# ScopeX.net
KiCad netlist of a schematic drawn in EAGLE
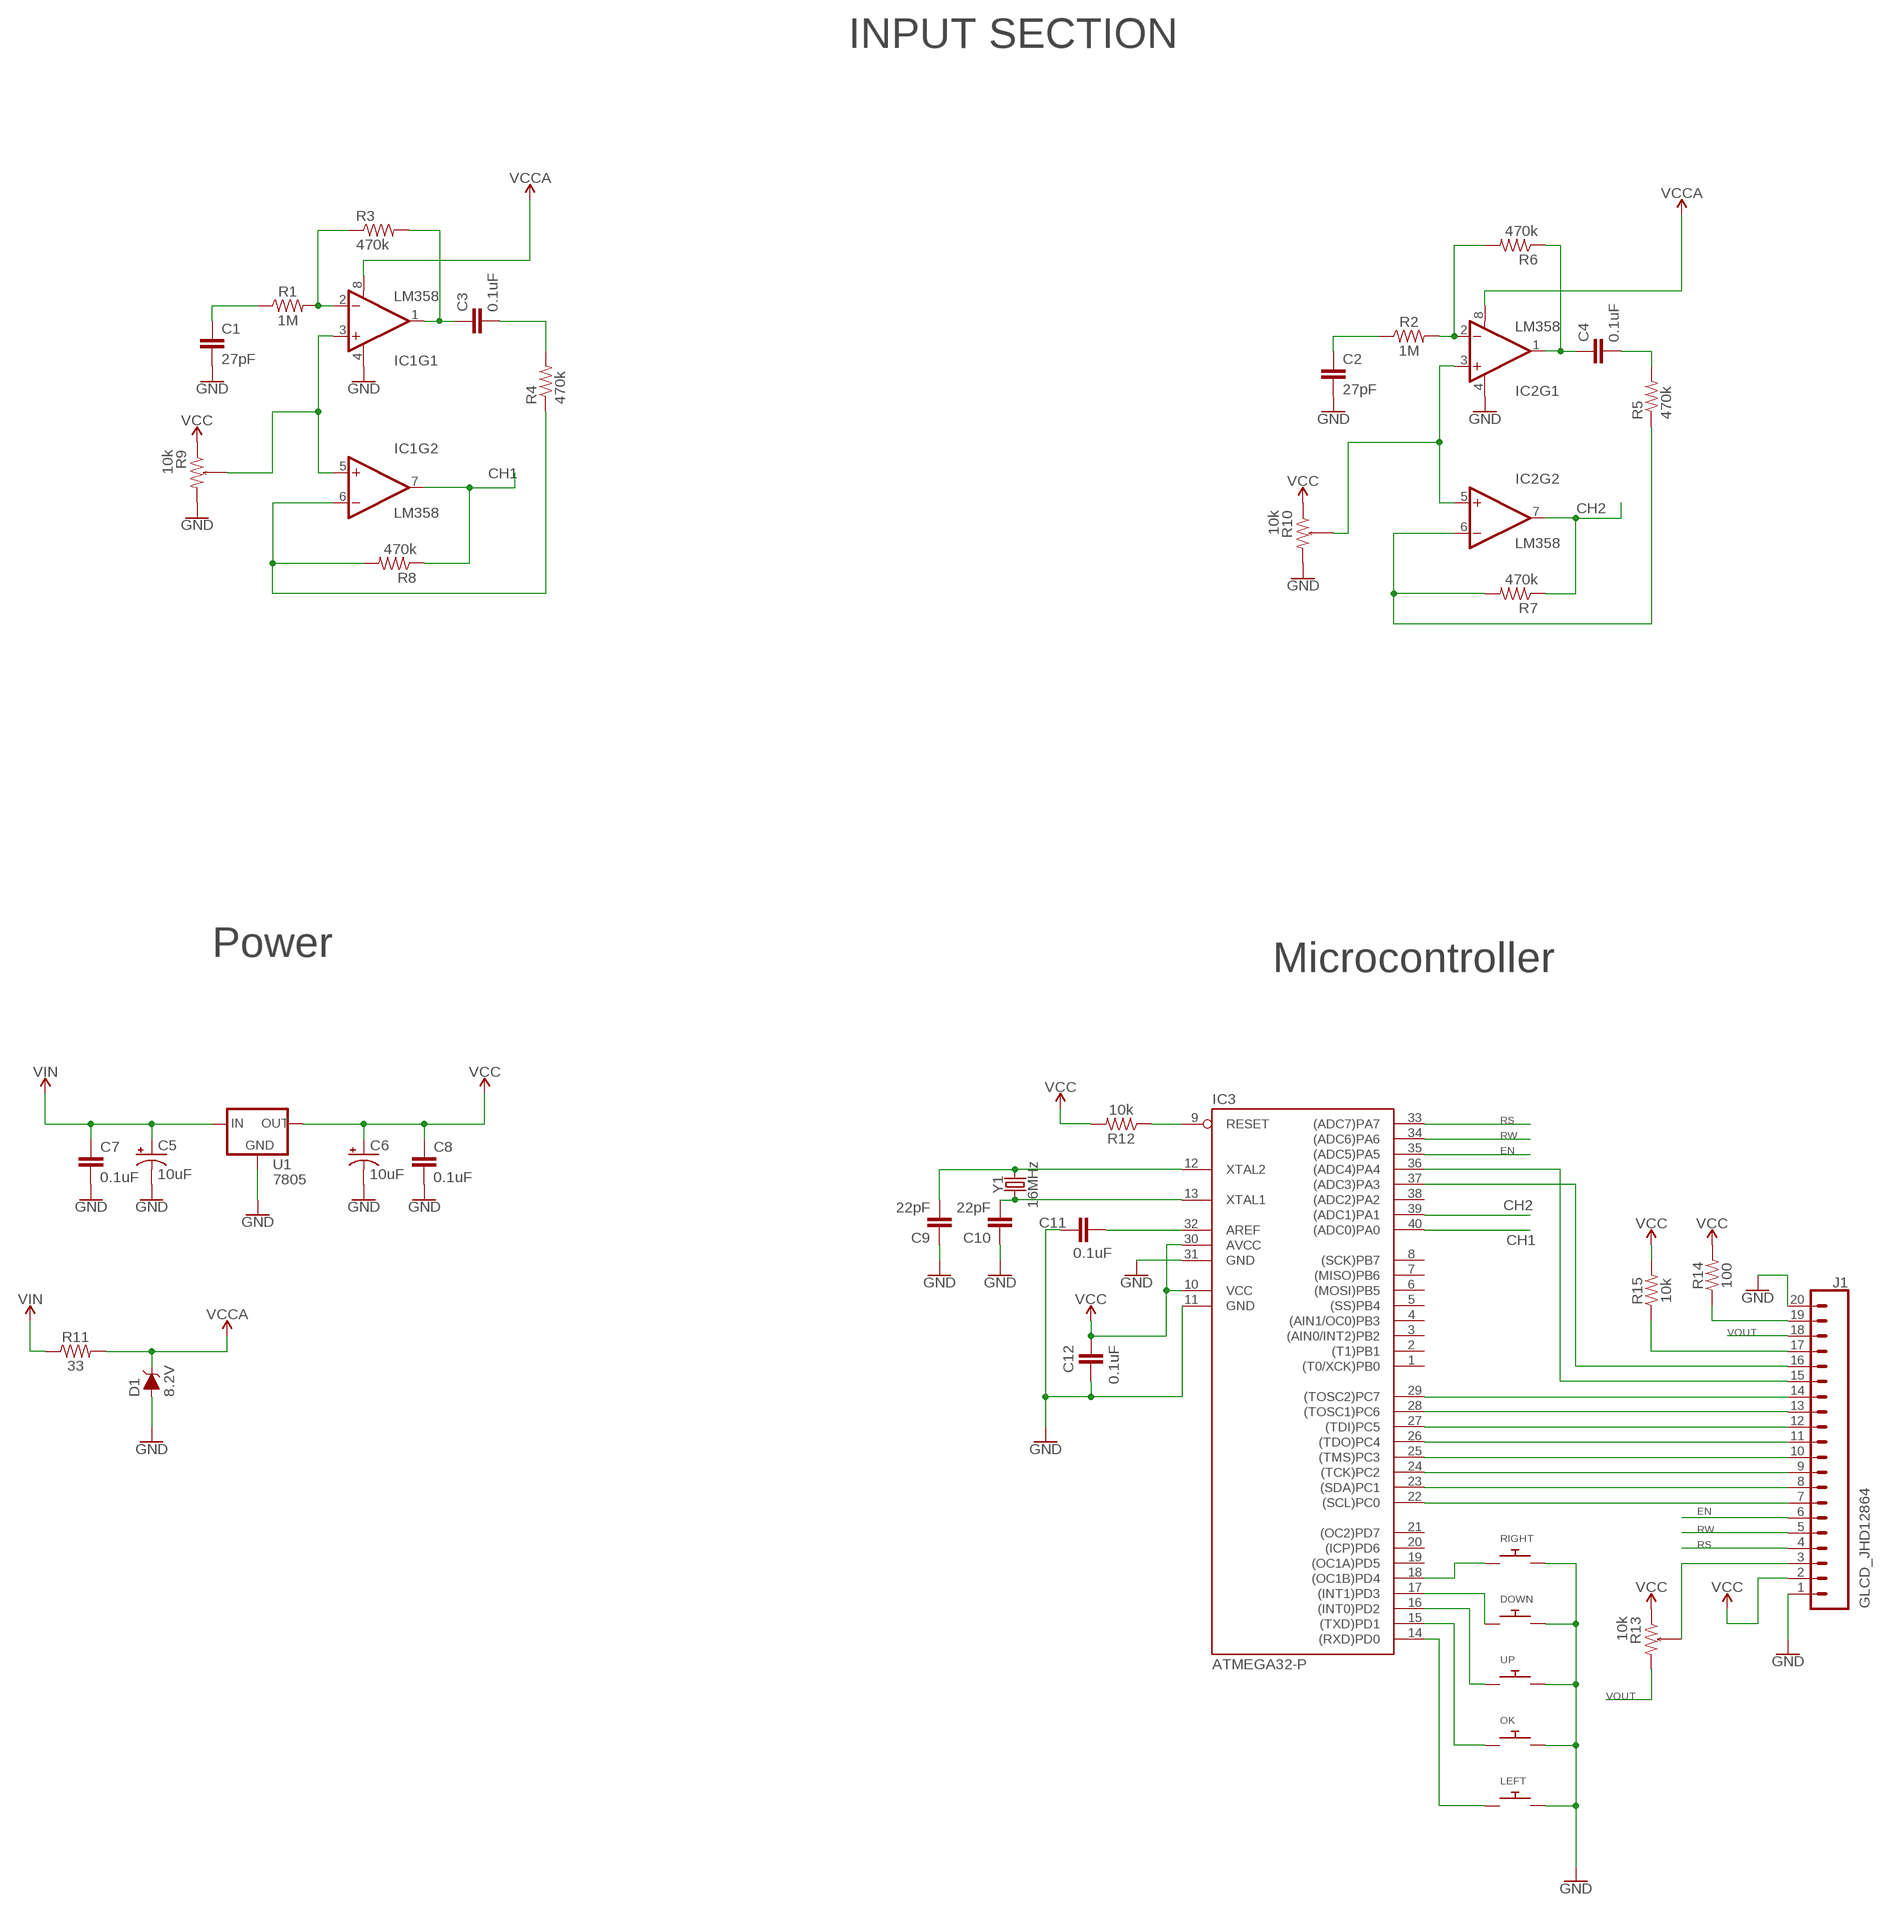
[diagram p0: schematic, sheet 1]

(export (version "E")
  (design (tool "Eeschema 10.0.6"))
  (components
    (comp (ref "C1")
      (value "27pF")
      (footprint "eagle-import:0603")
      (libsource (lib "eagle-import") (part "27PF-0603-50V-5%"))
    )
    (comp (ref "C2")
      (value "27pF")
      (footprint "eagle-import:0603")
      (libsource (lib "eagle-import") (part "27PF-0603-50V-5%"))
    )
    (comp (ref "C3")
      (value "0.1uF")
      (footprint "eagle-import:0603")
      (libsource (lib "eagle-import") (part "0.1UF-0603-25V-(+80/-20%)"))
    )
    (comp (ref "C4")
      (value "0.1uF")
      (footprint "eagle-import:0603")
      (libsource (lib "eagle-import") (part "0.1UF-0603-25V-(+80/-20%)"))
    )
    (comp (ref "C5")
      (value "10uF")
      (footprint "eagle-import:CPOL-RADIAL-10UF-25V")
      (libsource (lib "eagle-import") (part "CAP_POLPTH2"))
    )
    (comp (ref "C6")
      (value "10uF")
      (footprint "eagle-import:CPOL-RADIAL-10UF-25V")
      (libsource (lib "eagle-import") (part "CAP_POLPTH2"))
    )
    (comp (ref "C7")
      (value "0.1uF")
      (footprint "eagle-import:1206")
      (libsource (lib "eagle-import") (part "CAP1206"))
    )
    (comp (ref "C8")
      (value "0.1uF")
      (footprint "eagle-import:1206")
      (libsource (lib "eagle-import") (part "CAP1206"))
    )
    (comp (ref "C9")
      (value "22pF")
      (footprint "eagle-import:0603")
      (libsource (lib "eagle-import") (part "22PF-0603-50V-5%"))
    )
    (comp (ref "C10")
      (value "22pF")
      (footprint "eagle-import:0603")
      (libsource (lib "eagle-import") (part "22PF-0603-50V-5%"))
    )
    (comp (ref "C11")
      (value "0.1uF")
      (footprint "eagle-import:0603")
      (libsource (lib "eagle-import") (part "0.1UF-0603-25V-(+80/-20%)"))
    )
    (comp (ref "C12")
      (value "0.1uF")
      (footprint "eagle-import:0603")
      (libsource (lib "eagle-import") (part "0.1UF-0603-25V-(+80/-20%)"))
    )
    (comp (ref "D1")
      (value "8.2V")
      (footprint "eagle-import:SOD-323")
      (libsource (lib "eagle-import") (part "DIODE-ZENER-MMSZ5232BS"))
    )
    (comp (ref "DOWN")
      (value "SWITCH_PUSHBUTTONSOFTTOUCHSMD_SJ")
      (footprint "eagle-import:PUSHBUTTON_SMD_SJ")
      (libsource (lib "eagle-import") (part "SWITCH_PUSHBUTTONSOFTTOUCHSMD_SJ"))
    )
    (comp (ref "IC1")
      (value "LM358")
      (footprint "eagle-import:DIP08")
      (libsource (lib "eagle-import") (part "LM358"))
    )
    (comp (ref "IC2")
      (value "LM358")
      (footprint "eagle-import:DIP08")
      (libsource (lib "eagle-import") (part "LM358"))
    )
    (comp (ref "IC3")
      (value "ATMEGA32-P")
      (footprint "eagle-import:DIL40")
      (fields (field (name "MPN") "ATMEGA32-16PU"))
      (libsource (lib "eagle-import") (part "MEGA32-P"))
    )
    (comp (ref "J1")
      (value "GLCD_JHD12864")
      (footprint "eagle-import:1X20")
      (libsource (lib "eagle-import") (part "CONN_20"))
    )
    (comp (ref "LEFT")
      (value "SWITCH_PUSHBUTTONSOFTTOUCHSMD_SJ")
      (footprint "eagle-import:PUSHBUTTON_SMD_SJ")
      (libsource (lib "eagle-import") (part "SWITCH_PUSHBUTTONSOFTTOUCHSMD_SJ"))
    )
    (comp (ref "OK")
      (value "SWITCH_PUSHBUTTONSOFTTOUCHSMD_SJ")
      (footprint "eagle-import:PUSHBUTTON_SMD_SJ")
      (libsource (lib "eagle-import") (part "SWITCH_PUSHBUTTONSOFTTOUCHSMD_SJ"))
    )
    (comp (ref "R1")
      (value "1M")
      (footprint "eagle-import:0603")
      (libsource (lib "eagle-import") (part "1MOHM-0603-1/4W-5%"))
    )
    (comp (ref "R2")
      (value "1M")
      (footprint "eagle-import:0603")
      (libsource (lib "eagle-import") (part "1MOHM-0603-1/4W-5%"))
    )
    (comp (ref "R3")
      (value "470k")
      (footprint "eagle-import:0603-RES")
      (libsource (lib "eagle-import") (part "RESISTOR0603-RES"))
    )
    (comp (ref "R4")
      (value "470k")
      (footprint "eagle-import:0603-RES")
      (libsource (lib "eagle-import") (part "RESISTOR0603-RES"))
    )
    (comp (ref "R5")
      (value "470k")
      (footprint "eagle-import:0603-RES")
      (libsource (lib "eagle-import") (part "RESISTOR0603-RES"))
    )
    (comp (ref "R6")
      (value "470k")
      (footprint "eagle-import:0603-RES")
      (libsource (lib "eagle-import") (part "RESISTOR0603-RES"))
    )
    (comp (ref "R7")
      (value "470k")
      (footprint "eagle-import:0603-RES")
      (libsource (lib "eagle-import") (part "RESISTOR0603-RES"))
    )
    (comp (ref "R8")
      (value "470k")
      (footprint "eagle-import:0603-RES")
      (libsource (lib "eagle-import") (part "RESISTOR0603-RES"))
    )
    (comp (ref "R9")
      (value "10k")
      (footprint "eagle-import:0603-ARV")
      (libsource (lib "eagle-import") (part "POTENTIOMETER"))
    )
    (comp (ref "R10")
      (value "10k")
      (footprint "eagle-import:0603-ARV")
      (libsource (lib "eagle-import") (part "POTENTIOMETER"))
    )
    (comp (ref "R11")
      (value "33")
      (footprint "eagle-import:0603")
      (libsource (lib "eagle-import") (part "33OHM-0603-1/10W-1%"))
    )
    (comp (ref "R12")
      (value "10k")
      (footprint "eagle-import:0603")
      (libsource (lib "eagle-import") (part "10KOHM-0603-1/10W-1%"))
    )
    (comp (ref "R13")
      (value "10k")
      (footprint "eagle-import:0603-ARV")
      (libsource (lib "eagle-import") (part "POTENTIOMETER"))
    )
    (comp (ref "R14")
      (value "100")
      (footprint "eagle-import:0603")
      (libsource (lib "eagle-import") (part "100OHM-0603-1/4W-5%"))
    )
    (comp (ref "R15")
      (value "10k")
      (footprint "eagle-import:0603")
      (libsource (lib "eagle-import") (part "10KOHM-0603-1/10W-1%"))
    )
    (comp (ref "RIGHT")
      (value "SWITCH_PUSHBUTTONSOFTTOUCHSMD_SJ")
      (footprint "eagle-import:PUSHBUTTON_SMD_SJ")
      (libsource (lib "eagle-import") (part "SWITCH_PUSHBUTTONSOFTTOUCHSMD_SJ"))
    )
    (comp (ref "U1")
      (value "7805")
      (footprint "eagle-import:TO-220-ALT")
      (libsource (lib "eagle-import") (part "V_REG_78XX-TO-220"))
    )
    (comp (ref "UP")
      (value "SWITCH_PUSHBUTTONSOFTTOUCHSMD_SJ")
      (footprint "eagle-import:PUSHBUTTON_SMD_SJ")
      (libsource (lib "eagle-import") (part "SWITCH_PUSHBUTTONSOFTTOUCHSMD_SJ"))
    )
    (comp (ref "Y1")
      (value "16MHz")
      (footprint "eagle-import:HC49US")
      (libsource (lib "eagle-import") (part "CRYSTAL-16MHZPTH-HC49US"))
    )
  )
  (nets
    (net (code "1") (name "/CH1") (class "Default")
      (node (ref "IC1") (pin "7") (pinfunction "OUT_7") (pintype "output"))
      (node (ref "IC3") (pin "40") (pinfunction "(ADC0)PA0_40") (pintype "bidirectional"))
      (node (ref "R8") (pin "1") (pinfunction "1_1") (pintype "passive"))
    )
    (net (code "2") (name "/CH2") (class "Default")
      (node (ref "IC2") (pin "7") (pinfunction "OUT_7") (pintype "output"))
      (node (ref "IC3") (pin "39") (pinfunction "(ADC1)PA1_39") (pintype "bidirectional"))
      (node (ref "R7") (pin "1") (pinfunction "1_1") (pintype "passive"))
    )
    (net (code "3") (name "/EN") (class "Default")
      (node (ref "IC3") (pin "35") (pinfunction "(ADC5)PA5_35") (pintype "bidirectional"))
      (node (ref "J1") (pin "6") (pinfunction "6_6") (pintype "passive"))
    )
    (net (code "4") (name "/RS") (class "Default")
      (node (ref "IC3") (pin "33") (pinfunction "(ADC7)PA7_33") (pintype "bidirectional"))
      (node (ref "J1") (pin "4") (pinfunction "4_4") (pintype "passive"))
    )
    (net (code "5") (name "/RW") (class "Default")
      (node (ref "IC3") (pin "34") (pinfunction "(ADC6)PA6_34") (pintype "bidirectional"))
      (node (ref "J1") (pin "5") (pinfunction "5_5") (pintype "passive"))
    )
    (net (code "6") (name "/VOUT") (class "Default")
      (node (ref "J1") (pin "18") (pinfunction "18_18") (pintype "passive"))
      (node (ref "R13") (pin "2") (pinfunction "2_2") (pintype "passive"))
    )
    (net (code "7") (name "GND") (class "Default")
      (node (ref "C1") (pin "2") (pinfunction "2_2") (pintype "passive"))
      (node (ref "C10") (pin "1") (pinfunction "1_1") (pintype "passive"))
      (node (ref "C11") (pin "1") (pinfunction "1_1") (pintype "passive"))
      (node (ref "C12") (pin "1") (pinfunction "1_1") (pintype "passive"))
      (node (ref "C2") (pin "2") (pinfunction "2_2") (pintype "passive"))
      (node (ref "C5") (pin "2") (pinfunction "-_2") (pintype "passive"))
      (node (ref "C6") (pin "2") (pinfunction "-_2") (pintype "passive"))
      (node (ref "C7") (pin "2") (pinfunction "2_2") (pintype "passive"))
      (node (ref "C8") (pin "2") (pinfunction "2_2") (pintype "passive"))
      (node (ref "C9") (pin "1") (pinfunction "1_1") (pintype "passive"))
      (node (ref "D1") (pin "A") (pinfunction "A_A") (pintype "passive"))
      (node (ref "DOWN") (pin "P$2") (pinfunction "P$2_P$2") (pintype "passive"))
      (node (ref "IC1") (pin "4") (pinfunction "V-_4") (pintype "power_in"))
      (node (ref "IC2") (pin "4") (pinfunction "V-_4") (pintype "power_in"))
      (node (ref "IC3") (pin "11") (pinfunction "GND_11") (pintype "power_in"))
      (node (ref "IC3") (pin "31") (pinfunction "GND_31") (pintype "power_in"))
      (node (ref "J1") (pin "1") (pinfunction "1_1") (pintype "passive"))
      (node (ref "J1") (pin "20") (pinfunction "20_20") (pintype "passive"))
      (node (ref "LEFT") (pin "P$2") (pinfunction "P$2_P$2") (pintype "passive"))
      (node (ref "OK") (pin "P$2") (pinfunction "P$2_P$2") (pintype "passive"))
      (node (ref "R10") (pin "2") (pinfunction "2_2") (pintype "passive"))
      (node (ref "R9") (pin "2") (pinfunction "2_2") (pintype "passive"))
      (node (ref "RIGHT") (pin "P$2") (pinfunction "P$2_P$2") (pintype "passive"))
      (node (ref "U1") (pin "GND") (pinfunction "GND_GND") (pintype "input"))
      (node (ref "UP") (pin "P$2") (pinfunction "P$2_P$2") (pintype "passive"))
    )
    (net (code "8") (name "Net-(C1-Pad1)") (class "Default")
      (node (ref "C1") (pin "1") (pinfunction "1_1") (pintype "passive"))
      (node (ref "R1") (pin "1") (pinfunction "1_1") (pintype "passive"))
    )
    (net (code "9") (name "Net-(C2-Pad1)") (class "Default")
      (node (ref "C2") (pin "1") (pinfunction "1_1") (pintype "passive"))
      (node (ref "R2") (pin "1") (pinfunction "1_1") (pintype "passive"))
    )
    (net (code "10") (name "Net-(C3-Pad2)") (class "Default")
      (node (ref "C3") (pin "2") (pinfunction "2_2") (pintype "passive"))
      (node (ref "R4") (pin "2") (pinfunction "2_2") (pintype "passive"))
    )
    (net (code "11") (name "Net-(C4-Pad2)") (class "Default")
      (node (ref "C4") (pin "2") (pinfunction "2_2") (pintype "passive"))
      (node (ref "R5") (pin "2") (pinfunction "2_2") (pintype "passive"))
    )
    (net (code "12") (name "Net-(IC1A-+IN)") (class "Default")
      (node (ref "IC1") (pin "3") (pinfunction "+IN_3") (pintype "input"))
      (node (ref "IC1") (pin "5") (pinfunction "+IN_5") (pintype "input"))
      (node (ref "R9") (pin "3") (pinfunction "P$1_3") (pintype "bidirectional"))
      (node (ref "R9") (pin "4") (pinfunction "P$1_4") (pintype "bidirectional"))
      (node (ref "R9") (pin "5") (pinfunction "P$1_5") (pintype "bidirectional"))
      (node (ref "R9") (pin "6") (pinfunction "P$1_6") (pintype "bidirectional"))
      (node (ref "R9") (pin "7") (pinfunction "P$1_7") (pintype "bidirectional"))
      (node (ref "R9") (pin "8") (pinfunction "P$1_8") (pintype "bidirectional"))
    )
    (net (code "13") (name "Net-(IC1A--IN)") (class "Default")
      (node (ref "IC1") (pin "2") (pinfunction "-IN_2") (pintype "input"))
      (node (ref "R1") (pin "2") (pinfunction "2_2") (pintype "passive"))
      (node (ref "R3") (pin "1") (pinfunction "1_1") (pintype "passive"))
    )
    (net (code "14") (name "Net-(IC1A-OUT)") (class "Default")
      (node (ref "C3") (pin "1") (pinfunction "1_1") (pintype "passive"))
      (node (ref "IC1") (pin "1") (pinfunction "OUT_1") (pintype "output"))
      (node (ref "R3") (pin "2") (pinfunction "2_2") (pintype "passive"))
    )
    (net (code "15") (name "Net-(IC1B--IN)") (class "Default")
      (node (ref "IC1") (pin "6") (pinfunction "-IN_6") (pintype "input"))
      (node (ref "R4") (pin "1") (pinfunction "1_1") (pintype "passive"))
      (node (ref "R8") (pin "2") (pinfunction "2_2") (pintype "passive"))
    )
    (net (code "16") (name "Net-(IC2A-+IN)") (class "Default")
      (node (ref "IC2") (pin "3") (pinfunction "+IN_3") (pintype "input"))
      (node (ref "IC2") (pin "5") (pinfunction "+IN_5") (pintype "input"))
      (node (ref "R10") (pin "3") (pinfunction "P$1_3") (pintype "bidirectional"))
      (node (ref "R10") (pin "4") (pinfunction "P$1_4") (pintype "bidirectional"))
      (node (ref "R10") (pin "5") (pinfunction "P$1_5") (pintype "bidirectional"))
      (node (ref "R10") (pin "6") (pinfunction "P$1_6") (pintype "bidirectional"))
      (node (ref "R10") (pin "7") (pinfunction "P$1_7") (pintype "bidirectional"))
      (node (ref "R10") (pin "8") (pinfunction "P$1_8") (pintype "bidirectional"))
    )
    (net (code "17") (name "Net-(IC2A--IN)") (class "Default")
      (node (ref "IC2") (pin "2") (pinfunction "-IN_2") (pintype "input"))
      (node (ref "R2") (pin "2") (pinfunction "2_2") (pintype "passive"))
      (node (ref "R6") (pin "2") (pinfunction "2_2") (pintype "passive"))
    )
    (net (code "18") (name "Net-(IC2A-OUT)") (class "Default")
      (node (ref "C4") (pin "1") (pinfunction "1_1") (pintype "passive"))
      (node (ref "IC2") (pin "1") (pinfunction "OUT_1") (pintype "output"))
      (node (ref "R6") (pin "1") (pinfunction "1_1") (pintype "passive"))
    )
    (net (code "19") (name "Net-(IC2B--IN)") (class "Default")
      (node (ref "IC2") (pin "6") (pinfunction "-IN_6") (pintype "input"))
      (node (ref "R5") (pin "1") (pinfunction "1_1") (pintype "passive"))
      (node (ref "R7") (pin "2") (pinfunction "2_2") (pintype "passive"))
    )
    (net (code "20") (name "Net-(IC3-(ADC3)PA3)") (class "Default")
      (node (ref "IC3") (pin "37") (pinfunction "(ADC3)PA3_37") (pintype "bidirectional"))
      (node (ref "J1") (pin "16") (pinfunction "16_16") (pintype "passive"))
    )
    (net (code "21") (name "Net-(IC3-(ADC4)PA4)") (class "Default")
      (node (ref "IC3") (pin "36") (pinfunction "(ADC4)PA4_36") (pintype "bidirectional"))
      (node (ref "J1") (pin "15") (pinfunction "15_15") (pintype "passive"))
    )
    (net (code "22") (name "Net-(IC3-(INT0)PD2)") (class "Default")
      (node (ref "IC3") (pin "16") (pinfunction "(INT0)PD2_16") (pintype "bidirectional"))
      (node (ref "UP") (pin "P$1") (pinfunction "P$1_P$1") (pintype "passive"))
    )
    (net (code "23") (name "Net-(IC3-(INT1)PD3)") (class "Default")
      (node (ref "DOWN") (pin "P$1") (pinfunction "P$1_P$1") (pintype "passive"))
      (node (ref "IC3") (pin "17") (pinfunction "(INT1)PD3_17") (pintype "bidirectional"))
    )
    (net (code "24") (name "Net-(IC3-(OC1B)PD4)") (class "Default")
      (node (ref "IC3") (pin "18") (pinfunction "(OC1B)PD4_18") (pintype "bidirectional"))
      (node (ref "RIGHT") (pin "P$1") (pinfunction "P$1_P$1") (pintype "passive"))
    )
    (net (code "25") (name "Net-(IC3-(RXD)PD0)") (class "Default")
      (node (ref "IC3") (pin "14") (pinfunction "(RXD)PD0_14") (pintype "bidirectional"))
      (node (ref "LEFT") (pin "P$1") (pinfunction "P$1_P$1") (pintype "passive"))
    )
    (net (code "26") (name "Net-(IC3-(SCL)PC0)") (class "Default")
      (node (ref "IC3") (pin "22") (pinfunction "(SCL)PC0_22") (pintype "bidirectional"))
      (node (ref "J1") (pin "7") (pinfunction "7_7") (pintype "passive"))
    )
    (net (code "27") (name "Net-(IC3-(SDA)PC1)") (class "Default")
      (node (ref "IC3") (pin "23") (pinfunction "(SDA)PC1_23") (pintype "bidirectional"))
      (node (ref "J1") (pin "8") (pinfunction "8_8") (pintype "passive"))
    )
    (net (code "28") (name "Net-(IC3-(TCK)PC2)") (class "Default")
      (node (ref "IC3") (pin "24") (pinfunction "(TCK)PC2_24") (pintype "bidirectional"))
      (node (ref "J1") (pin "9") (pinfunction "9_9") (pintype "passive"))
    )
    (net (code "29") (name "Net-(IC3-(TDI)PC5)") (class "Default")
      (node (ref "IC3") (pin "27") (pinfunction "(TDI)PC5_27") (pintype "bidirectional"))
      (node (ref "J1") (pin "12") (pinfunction "12_12") (pintype "passive"))
    )
    (net (code "30") (name "Net-(IC3-(TDO)PC4)") (class "Default")
      (node (ref "IC3") (pin "26") (pinfunction "(TDO)PC4_26") (pintype "bidirectional"))
      (node (ref "J1") (pin "11") (pinfunction "11_11") (pintype "passive"))
    )
    (net (code "31") (name "Net-(IC3-(TMS)PC3)") (class "Default")
      (node (ref "IC3") (pin "25") (pinfunction "(TMS)PC3_25") (pintype "bidirectional"))
      (node (ref "J1") (pin "10") (pinfunction "10_10") (pintype "passive"))
    )
    (net (code "32") (name "Net-(IC3-(TOSC1)PC6)") (class "Default")
      (node (ref "IC3") (pin "28") (pinfunction "(TOSC1)PC6_28") (pintype "bidirectional"))
      (node (ref "J1") (pin "13") (pinfunction "13_13") (pintype "passive"))
    )
    (net (code "33") (name "Net-(IC3-(TOSC2)PC7)") (class "Default")
      (node (ref "IC3") (pin "29") (pinfunction "(TOSC2)PC7_29") (pintype "bidirectional"))
      (node (ref "J1") (pin "14") (pinfunction "14_14") (pintype "passive"))
    )
    (net (code "34") (name "Net-(IC3-(TXD)PD1)") (class "Default")
      (node (ref "IC3") (pin "15") (pinfunction "(TXD)PD1_15") (pintype "bidirectional"))
      (node (ref "OK") (pin "P$1") (pinfunction "P$1_P$1") (pintype "passive"))
    )
    (net (code "35") (name "Net-(IC3-AREF)") (class "Default")
      (node (ref "C11") (pin "2") (pinfunction "2_2") (pintype "passive"))
      (node (ref "IC3") (pin "32") (pinfunction "AREF_32") (pintype "passive"))
    )
    (net (code "36") (name "Net-(IC3-RESET)") (class "Default")
      (node (ref "IC3") (pin "9") (pinfunction "RESET_9") (pintype "input"))
      (node (ref "R12") (pin "1") (pinfunction "1_1") (pintype "passive"))
    )
    (net (code "37") (name "Net-(IC3-XTAL1)") (class "Default")
      (node (ref "C10") (pin "2") (pinfunction "2_2") (pintype "passive"))
      (node (ref "IC3") (pin "13") (pinfunction "XTAL1_13") (pintype "bidirectional"))
      (node (ref "Y1") (pin "1") (pinfunction "1_1") (pintype "passive"))
    )
    (net (code "38") (name "Net-(IC3-XTAL2)") (class "Default")
      (node (ref "C9") (pin "2") (pinfunction "2_2") (pintype "passive"))
      (node (ref "IC3") (pin "12") (pinfunction "XTAL2_12") (pintype "bidirectional"))
      (node (ref "Y1") (pin "2") (pinfunction "2_2") (pintype "passive"))
    )
    (net (code "39") (name "Net-(J1-Pad3)") (class "Default")
      (node (ref "J1") (pin "3") (pinfunction "3_3") (pintype "passive"))
      (node (ref "R13") (pin "3") (pinfunction "P$1_3") (pintype "bidirectional"))
      (node (ref "R13") (pin "4") (pinfunction "P$1_4") (pintype "bidirectional"))
      (node (ref "R13") (pin "5") (pinfunction "P$1_5") (pintype "bidirectional"))
      (node (ref "R13") (pin "6") (pinfunction "P$1_6") (pintype "bidirectional"))
      (node (ref "R13") (pin "7") (pinfunction "P$1_7") (pintype "bidirectional"))
      (node (ref "R13") (pin "8") (pinfunction "P$1_8") (pintype "bidirectional"))
    )
    (net (code "40") (name "Net-(J1-Pad17)") (class "Default")
      (node (ref "J1") (pin "17") (pinfunction "17_17") (pintype "passive"))
      (node (ref "R15") (pin "1") (pinfunction "1_1") (pintype "passive"))
    )
    (net (code "41") (name "Net-(J1-Pad19)") (class "Default")
      (node (ref "J1") (pin "19") (pinfunction "19_19") (pintype "passive"))
      (node (ref "R14") (pin "1") (pinfunction "1_1") (pintype "passive"))
    )
    (net (code "42") (name "VCC") (class "Default")
      (node (ref "C12") (pin "2") (pinfunction "2_2") (pintype "passive"))
      (node (ref "C6") (pin "1") (pinfunction "+_1") (pintype "passive"))
      (node (ref "C8") (pin "1") (pinfunction "1_1") (pintype "passive"))
      (node (ref "IC3") (pin "10") (pinfunction "VCC_10") (pintype "power_in"))
      (node (ref "IC3") (pin "30") (pinfunction "AVCC_30") (pintype "power_in"))
      (node (ref "J1") (pin "2") (pinfunction "2_2") (pintype "passive"))
      (node (ref "R10") (pin "1") (pinfunction "1_1") (pintype "passive"))
      (node (ref "R12") (pin "2") (pinfunction "2_2") (pintype "passive"))
      (node (ref "R13") (pin "1") (pinfunction "1_1") (pintype "passive"))
      (node (ref "R14") (pin "2") (pinfunction "2_2") (pintype "passive"))
      (node (ref "R15") (pin "2") (pinfunction "2_2") (pintype "passive"))
      (node (ref "R9") (pin "1") (pinfunction "1_1") (pintype "passive"))
      (node (ref "U1") (pin "OUT") (pinfunction "OUT_OUT") (pintype "output"))
    )
    (net (code "43") (name "VCCA") (class "Default")
      (node (ref "D1") (pin "C") (pinfunction "C_C") (pintype "passive"))
      (node (ref "IC1") (pin "8") (pinfunction "V+_8") (pintype "power_in"))
      (node (ref "IC2") (pin "8") (pinfunction "V+_8") (pintype "power_in"))
      (node (ref "R11") (pin "2") (pinfunction "2_2") (pintype "passive"))
    )
    (net (code "44") (name "VIN") (class "Default")
      (node (ref "C5") (pin "1") (pinfunction "+_1") (pintype "passive"))
      (node (ref "C7") (pin "1") (pinfunction "1_1") (pintype "passive"))
      (node (ref "R11") (pin "1") (pinfunction "1_1") (pintype "passive"))
      (node (ref "U1") (pin "IN") (pinfunction "IN_IN") (pintype "input"))
    )
    (net (code "45") (name "unconnected-(IC3-(ADC2)PA2-Pad38)") (class "Default")
      (node (ref "IC3") (pin "38") (pinfunction "(ADC2)PA2_38") (pintype "bidirectional"))
    )
    (net (code "46") (name "unconnected-(IC3-(AIN0{slash}INT2)PB2-Pad3)") (class "Default")
      (node (ref "IC3") (pin "3") (pinfunction "(AIN0/INT2)PB2_3") (pintype "bidirectional"))
    )
    (net (code "47") (name "unconnected-(IC3-(AIN1{slash}OC0)PB3-Pad4)") (class "Default")
      (node (ref "IC3") (pin "4") (pinfunction "(AIN1/OC0)PB3_4") (pintype "bidirectional"))
    )
    (net (code "48") (name "unconnected-(IC3-(ICP)PD6-Pad20)") (class "Default")
      (node (ref "IC3") (pin "20") (pinfunction "(ICP)PD6_20") (pintype "bidirectional"))
    )
    (net (code "49") (name "unconnected-(IC3-(MISO)PB6-Pad7)") (class "Default")
      (node (ref "IC3") (pin "7") (pinfunction "(MISO)PB6_7") (pintype "bidirectional"))
    )
    (net (code "50") (name "unconnected-(IC3-(MOSI)PB5-Pad6)") (class "Default")
      (node (ref "IC3") (pin "6") (pinfunction "(MOSI)PB5_6") (pintype "bidirectional"))
    )
    (net (code "51") (name "unconnected-(IC3-(OC1A)PD5-Pad19)") (class "Default")
      (node (ref "IC3") (pin "19") (pinfunction "(OC1A)PD5_19") (pintype "bidirectional"))
    )
    (net (code "52") (name "unconnected-(IC3-(OC2)PD7-Pad21)") (class "Default")
      (node (ref "IC3") (pin "21") (pinfunction "(OC2)PD7_21") (pintype "bidirectional"))
    )
    (net (code "53") (name "unconnected-(IC3-(SCK)PB7-Pad8)") (class "Default")
      (node (ref "IC3") (pin "8") (pinfunction "(SCK)PB7_8") (pintype "bidirectional"))
    )
    (net (code "54") (name "unconnected-(IC3-(SS)PB4-Pad5)") (class "Default")
      (node (ref "IC3") (pin "5") (pinfunction "(SS)PB4_5") (pintype "bidirectional"))
    )
    (net (code "55") (name "unconnected-(IC3-(T0{slash}XCK)PB0-Pad1)") (class "Default")
      (node (ref "IC3") (pin "1") (pinfunction "(T0/XCK)PB0_1") (pintype "bidirectional"))
    )
    (net (code "56") (name "unconnected-(IC3-(T1)PB1-Pad2)") (class "Default")
      (node (ref "IC3") (pin "2") (pinfunction "(T1)PB1_2") (pintype "bidirectional"))
    )
  )
)
